# Sheet3.net
KiCad netlist of a schematic drawn in Altium Designer
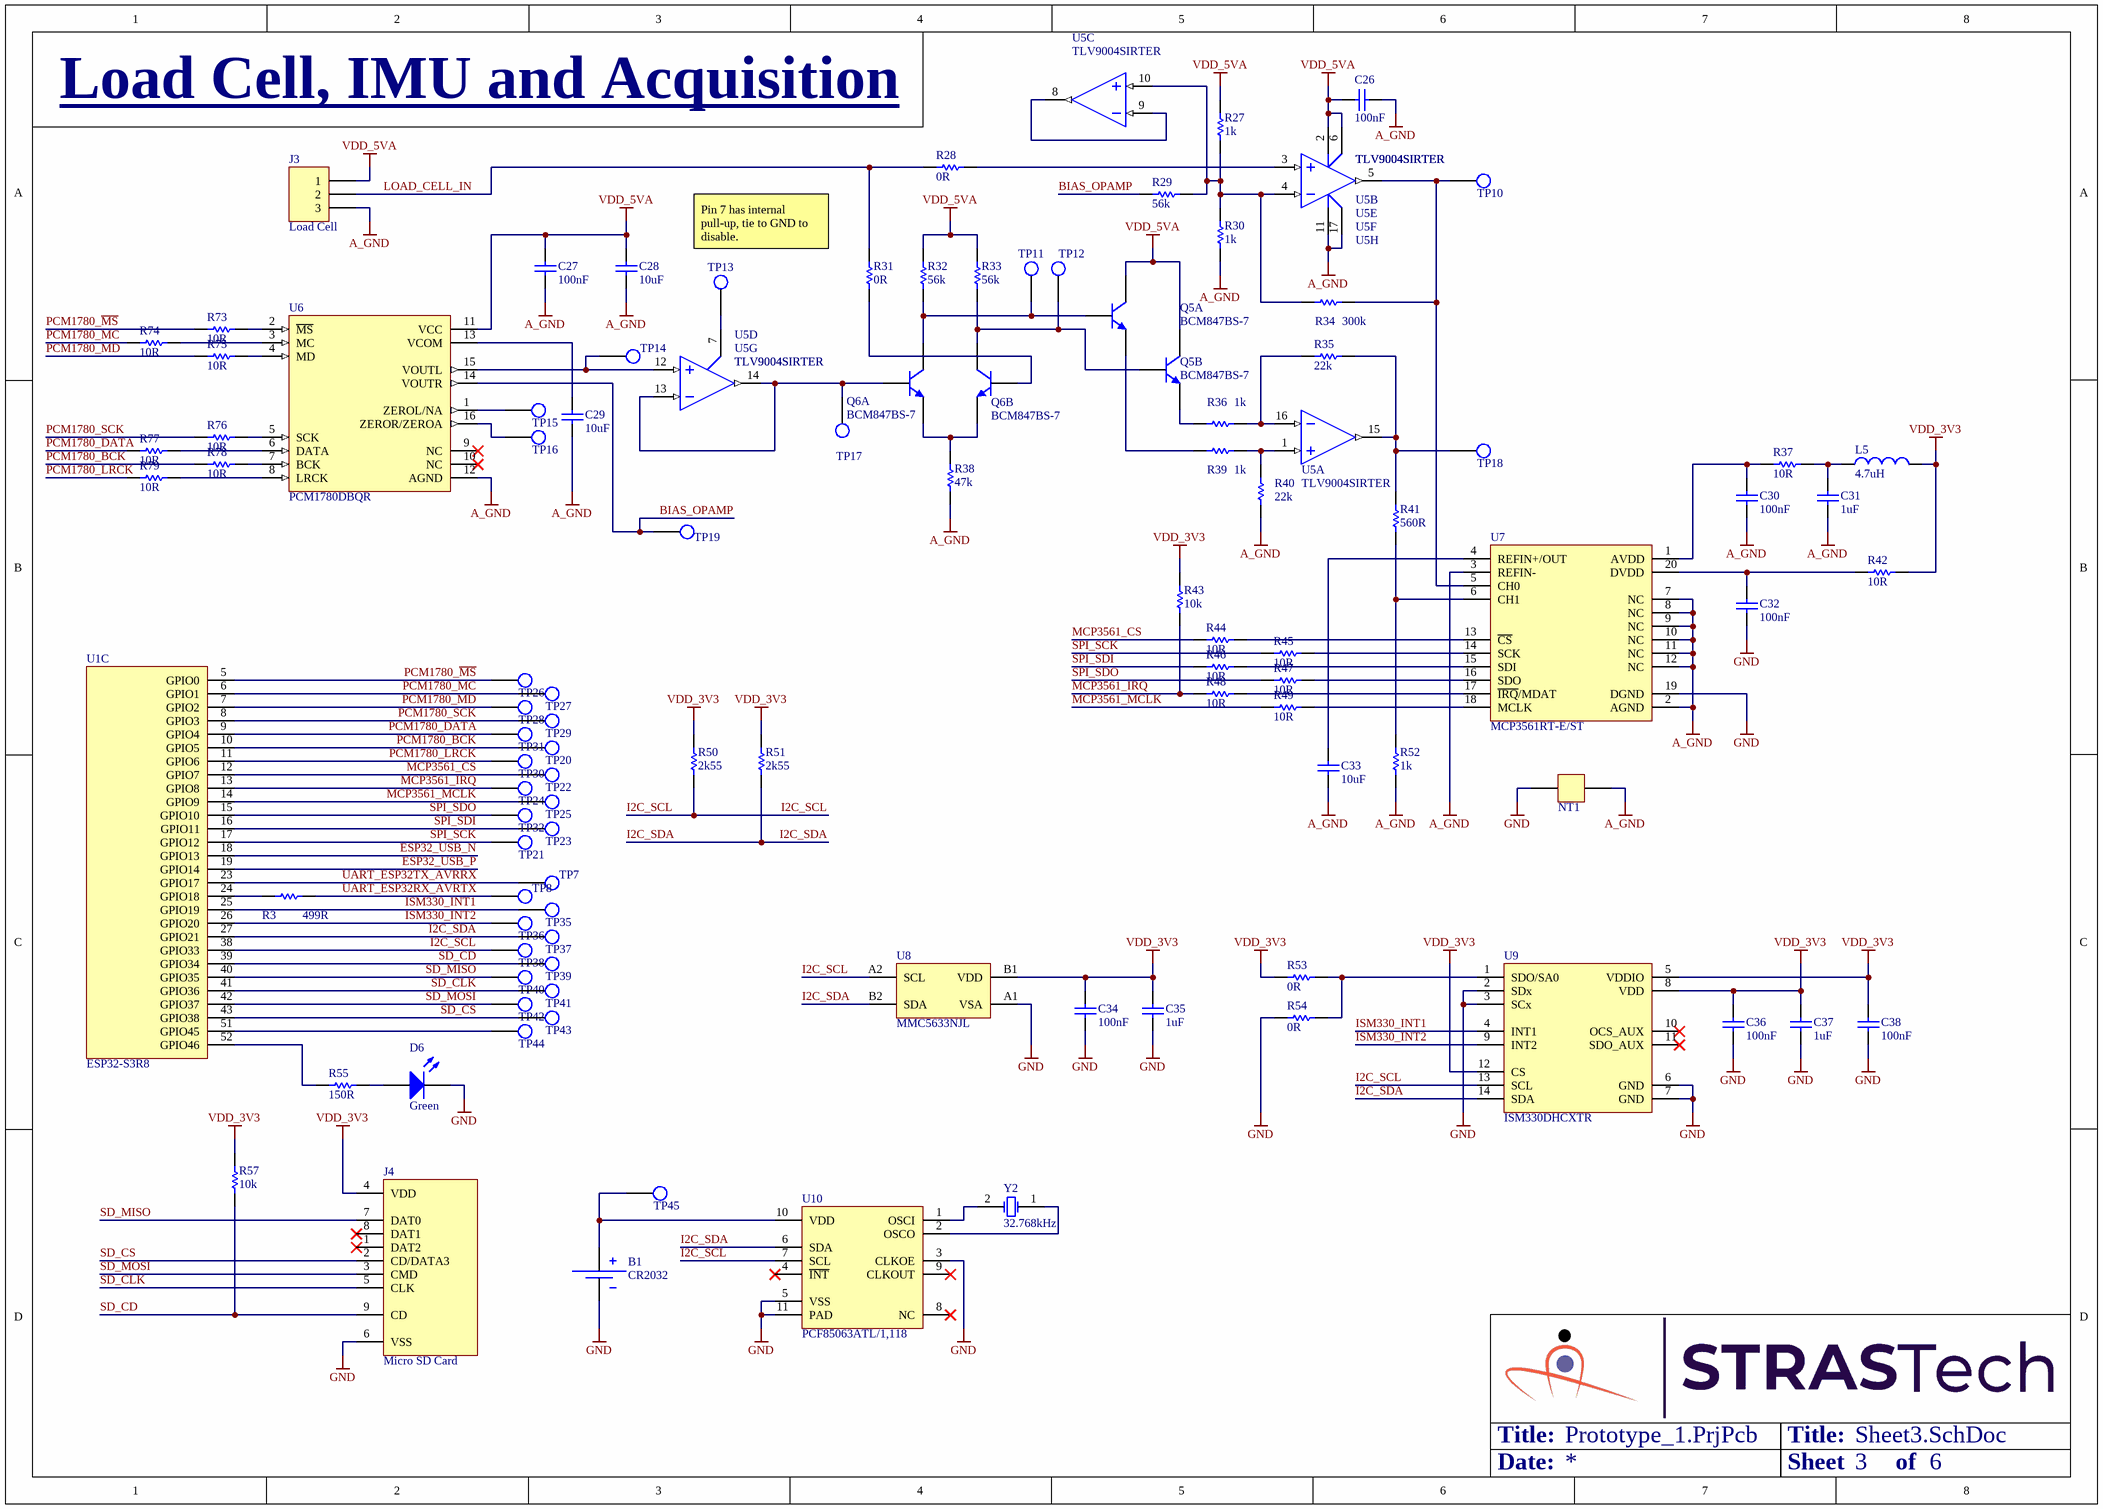
[diagram p0: Sheet3.SchDoc]

(export (version "E")
  (design (tool "Eeschema 10.0.6"))
  (components
    (comp (ref "B1")
      (value "CR2032")
      (footprint "Holder,Cell,CR2032,PCB,SMD")
      (description "Battery Retainer Coin, 20.0mm 1 Cell SMD (SMT) Tab")
      (fields
        (field (name "MANUFACTURER") "Keystone Electronics")
        (field (name "MANUFACTURER PART NUMBER") "3034")
        (field (name "CREATEDBY") "Judd Foster")
      )
      (libsource (lib "symbols") (part "Holder,Cell,CR2032,PCB,SMD"))
    )
    (comp (ref "C26")
      (value "100nF")
      (footprint "Cap,SMD,0402")
      (description "0.1µF ±10% 25V Ceramic Capacitor X7R 0402 (1005 Metric)")
      (fields
        (field (name "VENDOR PART NUMBER") "490-14603-1-ND")
        (field (name "MANUFACTURER") "Murata Electronics")
        (field (name "CREATEDBY") "Judd Foster")
      )
      (libsource (lib "symbols") (part "CAP,Cer,100nF,25VDC,X7R,0402"))
    )
    (comp (ref "C27")
      (value "100nF")
      (footprint "Cap,SMD,0402")
      (description "0.1µF ±10% 25V Ceramic Capacitor X7R 0402 (1005 Metric)")
      (fields
        (field (name "VENDOR PART NUMBER") "490-14603-1-ND")
        (field (name "MANUFACTURER") "Murata Electronics")
        (field (name "CREATEDBY") "Judd Foster")
      )
      (libsource (lib "symbols") (part "CAP,Cer,100nF,25VDC,X7R,0402"))
    )
    (comp (ref "C28")
      (value "10uF")
      (footprint "Cap,SMD,0402")
      (description "10 µF ±20% 10V Ceramic Capacitor X5R 0402 (1005 Metric)")
      (fields
        (field (name "VENDOR PART NUMBER") "1276-1450-1-ND")
        (field (name "MANUFACTURER") "Samsung Electro-Mechanics")
        (field (name "CREATEDBY") "Judd Foster")
      )
      (libsource (lib "symbols") (part "CAP,Cer,10uF,10VDC,X5R,0402"))
    )
    (comp (ref "C29")
      (value "10uF")
      (footprint "Cap,SMD,0402")
      (description "10 µF ±20% 10V Ceramic Capacitor X5R 0402 (1005 Metric)")
      (fields
        (field (name "VENDOR PART NUMBER") "1276-1450-1-ND")
        (field (name "MANUFACTURER") "Samsung Electro-Mechanics")
        (field (name "CREATEDBY") "Judd Foster")
      )
      (libsource (lib "symbols") (part "CAP,Cer,10uF,10VDC,X5R,0402"))
    )
    (comp (ref "C30")
      (value "100nF")
      (footprint "Cap,SMD,0402")
      (description "0.1µF ±10% 25V Ceramic Capacitor X7R 0402 (1005 Metric)")
      (fields
        (field (name "VENDOR PART NUMBER") "490-14603-1-ND")
        (field (name "MANUFACTURER") "Murata Electronics")
        (field (name "CREATEDBY") "Judd Foster")
      )
      (libsource (lib "symbols") (part "CAP,Cer,100nF,25VDC,X7R,0402"))
    )
    (comp (ref "C31")
      (value "1uF")
      (footprint "Cap,SMD,0402")
      (description "1 µF ±10% 35V Ceramic Capacitor X5R 0402 (1005 Metric)")
      (fields
        (field (name "VENDOR PART NUMBER") "445-9073-1-ND")
        (field (name "MANUFACTURER") "TDK Corporation")
        (field (name "CREATEDBY") "Judd Foster")
      )
      (libsource (lib "symbols") (part "CAP,Cer,1uF,35VDC,X5R,0402"))
    )
    (comp (ref "C32")
      (value "100nF")
      (footprint "Cap,SMD,0402")
      (description "0.1µF ±10% 25V Ceramic Capacitor X7R 0402 (1005 Metric)")
      (fields
        (field (name "VENDOR PART NUMBER") "490-14603-1-ND")
        (field (name "MANUFACTURER") "Murata Electronics")
        (field (name "CREATEDBY") "Judd Foster")
      )
      (libsource (lib "symbols") (part "CAP,Cer,100nF,25VDC,X7R,0402"))
    )
    (comp (ref "C33")
      (value "10uF")
      (footprint "Cap,SMD,0402")
      (description "10 µF ±20% 10V Ceramic Capacitor X5R 0402 (1005 Metric)")
      (fields
        (field (name "VENDOR PART NUMBER") "1276-1450-1-ND")
        (field (name "MANUFACTURER") "Samsung Electro-Mechanics")
        (field (name "CREATEDBY") "Judd Foster")
      )
      (libsource (lib "symbols") (part "CAP,Cer,10uF,10VDC,X5R,0402"))
    )
    (comp (ref "C34")
      (value "100nF")
      (footprint "Cap,SMD,0402")
      (description "0.1µF ±10% 25V Ceramic Capacitor X7R 0402 (1005 Metric)")
      (fields
        (field (name "VENDOR PART NUMBER") "490-14603-1-ND")
        (field (name "MANUFACTURER") "Murata Electronics")
        (field (name "CREATEDBY") "Judd Foster")
      )
      (libsource (lib "symbols") (part "CAP,Cer,100nF,25VDC,X7R,0402"))
    )
    (comp (ref "C35")
      (value "1uF")
      (footprint "Cap,SMD,0402")
      (description "1 µF ±10% 35V Ceramic Capacitor X5R 0402 (1005 Metric)")
      (fields
        (field (name "VENDOR PART NUMBER") "445-9073-1-ND")
        (field (name "MANUFACTURER") "TDK Corporation")
        (field (name "CREATEDBY") "Judd Foster")
      )
      (libsource (lib "symbols") (part "CAP,Cer,1uF,35VDC,X5R,0402"))
    )
    (comp (ref "C36")
      (value "100nF")
      (footprint "Cap,SMD,0402")
      (description "0.1µF ±10% 25V Ceramic Capacitor X7R 0402 (1005 Metric)")
      (fields
        (field (name "VENDOR PART NUMBER") "490-14603-1-ND")
        (field (name "MANUFACTURER") "Murata Electronics")
        (field (name "CREATEDBY") "Judd Foster")
      )
      (libsource (lib "symbols") (part "CAP,Cer,100nF,25VDC,X7R,0402"))
    )
    (comp (ref "C37")
      (value "1uF")
      (footprint "Cap,SMD,0402")
      (description "1 µF ±10% 35V Ceramic Capacitor X5R 0402 (1005 Metric)")
      (fields
        (field (name "VENDOR PART NUMBER") "445-9073-1-ND")
        (field (name "MANUFACTURER") "TDK Corporation")
        (field (name "CREATEDBY") "Judd Foster")
      )
      (libsource (lib "symbols") (part "CAP,Cer,1uF,35VDC,X5R,0402"))
    )
    (comp (ref "C38")
      (value "100nF")
      (footprint "Cap,SMD,0402")
      (description "0.1µF ±10% 25V Ceramic Capacitor X7R 0402 (1005 Metric)")
      (fields
        (field (name "VENDOR PART NUMBER") "490-14603-1-ND")
        (field (name "MANUFACTURER") "Murata Electronics")
        (field (name "CREATEDBY") "Judd Foster")
      )
      (libsource (lib "symbols") (part "CAP,Cer,100nF,25VDC,X7R,0402"))
    )
    (comp (ref "D6")
      (value "Green")
      (footprint "LED,0603")
      (description "Green 530nm LED Indication - Discrete 3V 0603 (1608 Metric)")
      (fields
        (field (name "MANUFACTURER") "Stanley Electric Co")
        (field (name "MANUFACTURER PART NUMBER") "THG1111C-0005-TR")
        (field (name "CREATEDBY") "Judd Foster")
      )
      (libsource (lib "symbols") (part "LED,Green,SMD,0603"))
    )
    (comp (ref "J3")
      (value "Term,Header,3 Pin,Top,2.54mm")
      (footprint "Term,Header,3Pin,2.54mm")
      (description "CONN HEADER VERT 3POS 2.54MM")
      (fields
        (field (name "VENDOR PART NUMBER") "732-5316-ND")
        (field (name "MANUFACTURER") "Würth Elektronik")
        (field (name "CREATED BY") "Judd Foster")
      )
      (libsource (lib "symbols") (part "Term,Header,3 Pin,Top,2.54mm"))
    )
    (comp (ref "J4")
      (value "Micro SD Card")
      (footprint "Conn,MicroSD,Push-Push,SMD")
      (description "9 (8 + 1) Position Card Connector Secure Digital - microSD™ Surface Mount, Right Angle Gold")
      (fields
        (field (name "MANUFACTURER") "GCT")
        (field (name "MANUFACTURER PART NUMBER") "MEM2075-00-140-01-A")
        (field (name "CREATEDBY") "Judd Foster")
      )
      (libsource (lib "symbols") (part "Conn,MicroSD,SMD,Push-Push"))
    )
    (comp (ref "L5")
      (value "4.7uH")
      (footprint "IND,0805")
      (description "4.7 µH Shielded Multilayer Inductor 80 mA 300mOhm 0805 (2012 Metric)")
      (fields
        (field (name "VENDOR PART NUMBER") "445-3169-1-ND")
        (field (name "MANUFACTURER") "TDK Corporation")
        (field (name "CREATEDBY") "Judd Foster")
      )
      (libsource (lib "symbols") (part "IND,4.7uH,80mA,Multilayer,0805"))
    )
    (comp (ref "NT1")
      (value "Net Tie")
      (footprint "Net Tie,20x60mil")
      (fields (field (name "CREATEDBY") "Makan Mousavi"))
      (libsource (lib "symbols") (part "Net Tie"))
    )
    (comp (ref "Q5")
      (value "BCM847BS-7")
      (footprint "SOT363")
      (fields
        (field (name "MANUFACTURER") "Diodes Incorporated")
        (field (name "VENDOR PART NUMBER") "31-BCM847BS-7CT-ND")
        (field (name "CREATEDBY") "Judd Foster")
      )
      (libsource (lib "symbols") (part "Trans,Array,NPN/NPN,Matched,45V,100mA,SOT-363"))
    )
    (comp (ref "Q6")
      (value "BCM847BS-7")
      (footprint "SOT363")
      (fields
        (field (name "MANUFACTURER") "Diodes Incorporated")
        (field (name "VENDOR PART NUMBER") "31-BCM847BS-7CT-ND")
        (field (name "CREATEDBY") "Judd Foster")
      )
      (libsource (lib "symbols") (part "Trans,Array,NPN/NPN,Matched,45V,100mA,SOT-363"))
    )
    (comp (ref "R3")
      (value "499R")
      (footprint "RES,0402")
      (description "499 Ohms ±1% 0.063W, 1/16W Chip Resistor 0402 (1005 Metric) Automotive AEC-Q200 Thick Film")
      (fields
        (field (name "MANUFACTURER") "Stackpole Electronics Inc")
        (field (name "MANUFACTURER PART NUMBER") "RMCF0402FT499R")
        (field (name "CREATEDBY") "Judd Foster")
      )
      (libsource (lib "symbols") (part "RES,499R,1%,0.063W,0402"))
    )
    (comp (ref "R27")
      (value "1k")
      (footprint "RES,0402")
      (description "1 kOhms ±5% 0.063W, 1/16W Chip Resistor 0402 (1005 Metric) Automotive AEC-Q200 Thick Film")
      (fields
        (field (name "VENDOR PART NUMBER") "RMCF0402JT1K00CT-ND")
        (field (name "MANUFACTURER") "Stackpole Electronics Inc")
        (field (name "CREATEDBY") "Judd Foster")
      )
      (libsource (lib "symbols") (part "RES,1k,5%,0.063W,0402"))
    )
    (comp (ref "R28")
      (value "0R")
      (footprint "RES,0402")
      (description "0 Ohms Jumper 0.1W, 1/10W Chip Resistor 0402 (1005 Metric) Automotive AEC-Q200 Thick Film")
      (fields
        (field (name "MANUFACTURER") "Panasonic Electronic Components")
        (field (name "MANUFACTURER PART NUMBER") "ERJ-2GE0R00X")
        (field (name "CREATEDBY") "Judd Foster")
      )
      (libsource (lib "symbols") (part "RES,0R0,0.1W,0402"))
    )
    (comp (ref "R29")
      (value "56k")
      (footprint "RES,0402")
      (description "56 kOhms ±1% 0.1W, 1/10W Chip Resistor 0402 (1005 Metric) Automotive AEC-Q200 Thick Film")
      (fields
        (field (name "MANUFACTURER") "Panasonic Electronic Components")
        (field (name "MANUFACTURER PART NUMBER") "ERJ-2RKF5602X")
        (field (name "CREATEDBY") "Judd Foster")
      )
      (libsource (lib "symbols") (part "RES,56k,1%,0.063W,0402"))
    )
    (comp (ref "R30")
      (value "1k")
      (footprint "RES,0402")
      (description "1 kOhms ±5% 0.063W, 1/16W Chip Resistor 0402 (1005 Metric) Automotive AEC-Q200 Thick Film")
      (fields
        (field (name "VENDOR PART NUMBER") "RMCF0402JT1K00CT-ND")
        (field (name "MANUFACTURER") "Stackpole Electronics Inc")
        (field (name "CREATEDBY") "Judd Foster")
      )
      (libsource (lib "symbols") (part "RES,1k,5%,0.063W,0402"))
    )
    (comp (ref "R31")
      (value "0R")
      (footprint "RES,0402")
      (description "0 Ohms Jumper 0.1W, 1/10W Chip Resistor 0402 (1005 Metric) Automotive AEC-Q200 Thick Film")
      (fields
        (field (name "MANUFACTURER") "Panasonic Electronic Components")
        (field (name "MANUFACTURER PART NUMBER") "ERJ-2GE0R00X")
        (field (name "CREATEDBY") "Judd Foster")
      )
      (libsource (lib "symbols") (part "RES,0R0,0.1W,0402"))
    )
    (comp (ref "R32")
      (value "56k")
      (footprint "RES,0402")
      (description "56 kOhms ±1% 0.1W, 1/10W Chip Resistor 0402 (1005 Metric) Automotive AEC-Q200 Thick Film")
      (fields
        (field (name "MANUFACTURER") "Panasonic Electronic Components")
        (field (name "MANUFACTURER PART NUMBER") "ERJ-2RKF5602X")
        (field (name "CREATEDBY") "Judd Foster")
      )
      (libsource (lib "symbols") (part "RES,56k,1%,0.063W,0402"))
    )
    (comp (ref "R33")
      (value "56k")
      (footprint "RES,0402")
      (description "56 kOhms ±1% 0.1W, 1/10W Chip Resistor 0402 (1005 Metric) Automotive AEC-Q200 Thick Film")
      (fields
        (field (name "MANUFACTURER") "Panasonic Electronic Components")
        (field (name "MANUFACTURER PART NUMBER") "ERJ-2RKF5602X")
        (field (name "CREATEDBY") "Judd Foster")
      )
      (libsource (lib "symbols") (part "RES,56k,1%,0.063W,0402"))
    )
    (comp (ref "R34")
      (value "300k")
      (footprint "RES,0402")
      (description "300 kOhms ±1% 0.063W, 1/16W Chip Resistor 0402 (1005 Metric) Automotive AEC-Q200 Thick Film")
      (fields
        (field (name "MANUFACTURER") "Stackpole Electronics Inc")
        (field (name "MANUFACTURER PART NUMBER") "RMCF0402FT300K")
        (field (name "CREATEDBY") "Judd Foster")
      )
      (libsource (lib "symbols") (part "RES,300k,1%,0.063W,0402"))
    )
    (comp (ref "R35")
      (value "22k")
      (footprint "RES,0402")
      (description "22 kOhms ±1% 0.063W, 1/16W Chip Resistor 0402 (1005 Metric) Automotive AEC-Q200 Thick Film")
      (fields
        (field (name "VENDOR PART NUMBER") "RMCF0402FT22K0CT-ND")
        (field (name "MANUFACTURER") "Stackpole Electronics Inc")
        (field (name "CREATEDBY") "Judd Foster")
      )
      (libsource (lib "symbols") (part "RES,22k,1%,0.063W,0402"))
    )
    (comp (ref "R36")
      (value "1k")
      (footprint "RES,0402")
      (description "1 kOhms ±5% 0.063W, 1/16W Chip Resistor 0402 (1005 Metric) Automotive AEC-Q200 Thick Film")
      (fields
        (field (name "VENDOR PART NUMBER") "RMCF0402JT1K00CT-ND")
        (field (name "MANUFACTURER") "Stackpole Electronics Inc")
        (field (name "CREATEDBY") "Judd Foster")
      )
      (libsource (lib "symbols") (part "RES,1k,5%,0.063W,0402"))
    )
    (comp (ref "R37")
      (value "10R")
      (footprint "RES,0402")
      (description "10 Ohms ±1% 0.063W, 1/16W Chip Resistor 0402 (1005 Metric) Automotive AEC-Q200 Thick Film")
      (fields
        (field (name "MANUFACTURER") "Panasonic Electronic Components")
        (field (name "MANUFACTURER PART NUMBER") "ERJ-2RKF10R0X")
        (field (name "CREATEDBY") "Judd Foster")
      )
      (libsource (lib "symbols") (part "RES,10R,1%,0.063W,0402"))
    )
    (comp (ref "R38")
      (value "47k")
      (footprint "RES,0402")
      (description "47 kOhms ±1% 0.1W, 1/10W Chip Resistor 0402 (1005 Metric) Automotive AEC-Q200 Thick Film")
      (fields
        (field (name "MANUFACTURER") "Panasonic Electronic Components")
        (field (name "MANUFACTURER PART NUMBER") "ERJ-2RKF4702X")
        (field (name "CREATEDBY") "Judd Foster")
      )
      (libsource (lib "symbols") (part "RES,47k,1%,0.1W,0402"))
    )
    (comp (ref "R39")
      (value "1k")
      (footprint "RES,0402")
      (description "1 kOhms ±5% 0.063W, 1/16W Chip Resistor 0402 (1005 Metric) Automotive AEC-Q200 Thick Film")
      (fields
        (field (name "VENDOR PART NUMBER") "RMCF0402JT1K00CT-ND")
        (field (name "MANUFACTURER") "Stackpole Electronics Inc")
        (field (name "CREATEDBY") "Judd Foster")
      )
      (libsource (lib "symbols") (part "RES,1k,5%,0.063W,0402"))
    )
    (comp (ref "R40")
      (value "22k")
      (footprint "RES,0402")
      (description "22 kOhms ±1% 0.063W, 1/16W Chip Resistor 0402 (1005 Metric) Automotive AEC-Q200 Thick Film")
      (fields
        (field (name "VENDOR PART NUMBER") "RMCF0402FT22K0CT-ND")
        (field (name "MANUFACTURER") "Stackpole Electronics Inc")
        (field (name "CREATEDBY") "Judd Foster")
      )
      (libsource (lib "symbols") (part "RES,22k,1%,0.063W,0402"))
    )
    (comp (ref "R41")
      (value "560R")
      (footprint "RES,0402")
      (fields
        (field (name "MANUFACTURER") "TE Connectivity Passive Product")
        (field (name "MANUFACTURER PART NUMBER") "CRGCQ0402F560R")
        (field (name "VENDOR PART NUMBER") "A129624CT-ND")
        (field (name "CREATEDBY") "Judd Foster")
      )
      (libsource (lib "symbols") (part "RES,560R,1%,0.063W,0402"))
    )
    (comp (ref "R42")
      (value "10R")
      (footprint "RES,0402")
      (description "10 Ohms ±1% 0.063W, 1/16W Chip Resistor 0402 (1005 Metric) Automotive AEC-Q200 Thick Film")
      (fields
        (field (name "MANUFACTURER") "Panasonic Electronic Components")
        (field (name "MANUFACTURER PART NUMBER") "ERJ-2RKF10R0X")
        (field (name "CREATEDBY") "Judd Foster")
      )
      (libsource (lib "symbols") (part "RES,10R,1%,0.063W,0402"))
    )
    (comp (ref "R43")
      (value "10k")
      (footprint "RES,0402")
      (description "10 kOhms ±5% 0.063W, 1/16W Chip Resistor 0402 (1005 Metric) Automotive AEC-Q200 Thick Film")
      (fields
        (field (name "VENDOR PART NUMBER") "RMCF0402JT10K0CT-ND")
        (field (name "MANUFACTURER") "Stackpole Electronics Inc")
        (field (name "CREATEDBY") "Judd Foster")
      )
      (libsource (lib "symbols") (part "RES,10k,5%,0.063W,0402"))
    )
    (comp (ref "R44")
      (value "10R")
      (footprint "RES,0402")
      (description "10 Ohms ±1% 0.063W, 1/16W Chip Resistor 0402 (1005 Metric) Automotive AEC-Q200 Thick Film")
      (fields
        (field (name "MANUFACTURER") "Panasonic Electronic Components")
        (field (name "MANUFACTURER PART NUMBER") "ERJ-2RKF10R0X")
        (field (name "CREATEDBY") "Judd Foster")
      )
      (libsource (lib "symbols") (part "RES,10R,1%,0.063W,0402"))
    )
    (comp (ref "R45")
      (value "10R")
      (footprint "RES,0402")
      (description "10 Ohms ±1% 0.063W, 1/16W Chip Resistor 0402 (1005 Metric) Automotive AEC-Q200 Thick Film")
      (fields
        (field (name "MANUFACTURER") "Panasonic Electronic Components")
        (field (name "MANUFACTURER PART NUMBER") "ERJ-2RKF10R0X")
        (field (name "CREATEDBY") "Judd Foster")
      )
      (libsource (lib "symbols") (part "RES,10R,1%,0.063W,0402"))
    )
    (comp (ref "R46")
      (value "10R")
      (footprint "RES,0402")
      (description "10 Ohms ±1% 0.063W, 1/16W Chip Resistor 0402 (1005 Metric) Automotive AEC-Q200 Thick Film")
      (fields
        (field (name "MANUFACTURER") "Panasonic Electronic Components")
        (field (name "MANUFACTURER PART NUMBER") "ERJ-2RKF10R0X")
        (field (name "CREATEDBY") "Judd Foster")
      )
      (libsource (lib "symbols") (part "RES,10R,1%,0.063W,0402"))
    )
    (comp (ref "R47")
      (value "10R")
      (footprint "RES,0402")
      (description "10 Ohms ±1% 0.063W, 1/16W Chip Resistor 0402 (1005 Metric) Automotive AEC-Q200 Thick Film")
      (fields
        (field (name "MANUFACTURER") "Panasonic Electronic Components")
        (field (name "MANUFACTURER PART NUMBER") "ERJ-2RKF10R0X")
        (field (name "CREATEDBY") "Judd Foster")
      )
      (libsource (lib "symbols") (part "RES,10R,1%,0.063W,0402"))
    )
    (comp (ref "R48")
      (value "10R")
      (footprint "RES,0402")
      (description "10 Ohms ±1% 0.063W, 1/16W Chip Resistor 0402 (1005 Metric) Automotive AEC-Q200 Thick Film")
      (fields
        (field (name "MANUFACTURER") "Panasonic Electronic Components")
        (field (name "MANUFACTURER PART NUMBER") "ERJ-2RKF10R0X")
        (field (name "CREATEDBY") "Judd Foster")
      )
      (libsource (lib "symbols") (part "RES,10R,1%,0.063W,0402"))
    )
    (comp (ref "R49")
      (value "10R")
      (footprint "RES,0402")
      (description "10 Ohms ±1% 0.063W, 1/16W Chip Resistor 0402 (1005 Metric) Automotive AEC-Q200 Thick Film")
      (fields
        (field (name "MANUFACTURER") "Panasonic Electronic Components")
        (field (name "MANUFACTURER PART NUMBER") "ERJ-2RKF10R0X")
        (field (name "CREATEDBY") "Judd Foster")
      )
      (libsource (lib "symbols") (part "RES,10R,1%,0.063W,0402"))
    )
    (comp (ref "R50")
      (value "2k55")
      (footprint "RES,0402")
      (description "2.55 kOhms ±1% 0.063W, 1/16W Chip Resistor 0402 (1005 Metric) Automotive AEC-Q200 Thick Film")
      (fields
        (field (name "MANUFACTURER") "Stackpole Electronics Inc")
        (field (name "MANUFACTURER PART NUMBER") "RMCF0402FT2K55")
        (field (name "CREATEDBY") "Judd Foster")
      )
      (libsource (lib "symbols") (part "RES,2k55,1%,0.063W,0402"))
    )
    (comp (ref "R51")
      (value "2k55")
      (footprint "RES,0402")
      (description "2.55 kOhms ±1% 0.063W, 1/16W Chip Resistor 0402 (1005 Metric) Automotive AEC-Q200 Thick Film")
      (fields
        (field (name "MANUFACTURER") "Stackpole Electronics Inc")
        (field (name "MANUFACTURER PART NUMBER") "RMCF0402FT2K55")
        (field (name "CREATEDBY") "Judd Foster")
      )
      (libsource (lib "symbols") (part "RES,2k55,1%,0.063W,0402"))
    )
    (comp (ref "R52")
      (value "1k")
      (footprint "RES,0402")
      (description "1 kOhms ±5% 0.063W, 1/16W Chip Resistor 0402 (1005 Metric) Automotive AEC-Q200 Thick Film")
      (fields
        (field (name "VENDOR PART NUMBER") "RMCF0402JT1K00CT-ND")
        (field (name "MANUFACTURER") "Stackpole Electronics Inc")
        (field (name "CREATEDBY") "Judd Foster")
      )
      (libsource (lib "symbols") (part "RES,1k,5%,0.063W,0402"))
    )
    (comp (ref "R53")
      (value "0R")
      (footprint "RES,0402")
      (description "0 Ohms Jumper 0.1W, 1/10W Chip Resistor 0402 (1005 Metric) Automotive AEC-Q200 Thick Film")
      (fields
        (field (name "MANUFACTURER") "Panasonic Electronic Components")
        (field (name "MANUFACTURER PART NUMBER") "ERJ-2GE0R00X")
        (field (name "CREATEDBY") "Judd Foster")
      )
      (libsource (lib "symbols") (part "RES,0R0,0.1W,0402"))
    )
    (comp (ref "R54")
      (value "0R")
      (footprint "RES,0402")
      (description "0 Ohms Jumper 0.1W, 1/10W Chip Resistor 0402 (1005 Metric) Automotive AEC-Q200 Thick Film")
      (fields
        (field (name "MANUFACTURER") "Panasonic Electronic Components")
        (field (name "MANUFACTURER PART NUMBER") "ERJ-2GE0R00X")
        (field (name "CREATEDBY") "Judd Foster")
      )
      (libsource (lib "symbols") (part "RES,0R0,0.1W,0402"))
    )
    (comp (ref "R55")
      (value "150R")
      (footprint "RES,0402")
      (fields
        (field (name "MANUFACTURER") "TE Connectivity Passive Product")
        (field (name "MANUFACTURER PART NUMBER") "CRGCQ0402F150R")
        (field (name "VENDOR PART NUMBER") "A129617CT-ND")
        (field (name "CREATEDBY") "Judd Foster")
      )
      (libsource (lib "symbols") (part "RES,150R,1%,0.1W,0402"))
    )
    (comp (ref "R57")
      (value "10k")
      (footprint "RES,0402")
      (description "10 kOhms ±5% 0.063W, 1/16W Chip Resistor 0402 (1005 Metric) Automotive AEC-Q200 Thick Film")
      (fields
        (field (name "VENDOR PART NUMBER") "RMCF0402JT10K0CT-ND")
        (field (name "MANUFACTURER") "Stackpole Electronics Inc")
        (field (name "CREATEDBY") "Judd Foster")
      )
      (libsource (lib "symbols") (part "RES,10k,5%,0.063W,0402"))
    )
    (comp (ref "R73")
      (value "10R")
      (footprint "RES,0402")
      (description "10 Ohms ±1% 0.063W, 1/16W Chip Resistor 0402 (1005 Metric) Automotive AEC-Q200 Thick Film")
      (fields
        (field (name "MANUFACTURER") "Panasonic Electronic Components")
        (field (name "MANUFACTURER PART NUMBER") "ERJ-2RKF10R0X")
        (field (name "CREATEDBY") "Judd Foster")
      )
      (libsource (lib "symbols") (part "RES,10R,1%,0.063W,0402"))
    )
    (comp (ref "R74")
      (value "10R")
      (footprint "RES,0402")
      (description "10 Ohms ±1% 0.063W, 1/16W Chip Resistor 0402 (1005 Metric) Automotive AEC-Q200 Thick Film")
      (fields
        (field (name "MANUFACTURER") "Panasonic Electronic Components")
        (field (name "MANUFACTURER PART NUMBER") "ERJ-2RKF10R0X")
        (field (name "CREATEDBY") "Judd Foster")
      )
      (libsource (lib "symbols") (part "RES,10R,1%,0.063W,0402"))
    )
    (comp (ref "R75")
      (value "10R")
      (footprint "RES,0402")
      (description "10 Ohms ±1% 0.063W, 1/16W Chip Resistor 0402 (1005 Metric) Automotive AEC-Q200 Thick Film")
      (fields
        (field (name "MANUFACTURER") "Panasonic Electronic Components")
        (field (name "MANUFACTURER PART NUMBER") "ERJ-2RKF10R0X")
        (field (name "CREATEDBY") "Judd Foster")
      )
      (libsource (lib "symbols") (part "RES,10R,1%,0.063W,0402"))
    )
    (comp (ref "R76")
      (value "10R")
      (footprint "RES,0402")
      (description "10 Ohms ±1% 0.063W, 1/16W Chip Resistor 0402 (1005 Metric) Automotive AEC-Q200 Thick Film")
      (fields
        (field (name "MANUFACTURER") "Panasonic Electronic Components")
        (field (name "MANUFACTURER PART NUMBER") "ERJ-2RKF10R0X")
        (field (name "CREATEDBY") "Judd Foster")
      )
      (libsource (lib "symbols") (part "RES,10R,1%,0.063W,0402"))
    )
    (comp (ref "R77")
      (value "10R")
      (footprint "RES,0402")
      (description "10 Ohms ±1% 0.063W, 1/16W Chip Resistor 0402 (1005 Metric) Automotive AEC-Q200 Thick Film")
      (fields
        (field (name "MANUFACTURER") "Panasonic Electronic Components")
        (field (name "MANUFACTURER PART NUMBER") "ERJ-2RKF10R0X")
        (field (name "CREATEDBY") "Judd Foster")
      )
      (libsource (lib "symbols") (part "RES,10R,1%,0.063W,0402"))
    )
    (comp (ref "R78")
      (value "10R")
      (footprint "RES,0402")
      (description "10 Ohms ±1% 0.063W, 1/16W Chip Resistor 0402 (1005 Metric) Automotive AEC-Q200 Thick Film")
      (fields
        (field (name "MANUFACTURER") "Panasonic Electronic Components")
        (field (name "MANUFACTURER PART NUMBER") "ERJ-2RKF10R0X")
        (field (name "CREATEDBY") "Judd Foster")
      )
      (libsource (lib "symbols") (part "RES,10R,1%,0.063W,0402"))
    )
    (comp (ref "R79")
      (value "10R")
      (footprint "RES,0402")
      (description "10 Ohms ±1% 0.063W, 1/16W Chip Resistor 0402 (1005 Metric) Automotive AEC-Q200 Thick Film")
      (fields
        (field (name "MANUFACTURER") "Panasonic Electronic Components")
        (field (name "MANUFACTURER PART NUMBER") "ERJ-2RKF10R0X")
        (field (name "CREATEDBY") "Judd Foster")
      )
      (libsource (lib "symbols") (part "RES,10R,1%,0.063W,0402"))
    )
    (comp (ref "TP7")
      (value "TESTPOINT")
      (footprint "testpoint,smd,round,1mm")
      (description "PCB Testpoint")
      (fields (field (name "CREATEDBY") "Judd Foster"))
      (libsource (lib "symbols") (part "TESTPOINT"))
    )
    (comp (ref "TP8")
      (value "TESTPOINT")
      (footprint "testpoint,smd,round,1mm")
      (description "PCB Testpoint")
      (fields (field (name "CREATEDBY") "Judd Foster"))
      (libsource (lib "symbols") (part "TESTPOINT"))
    )
    (comp (ref "TP10")
      (value "TESTPOINT")
      (footprint "testpoint,smd,round,1mm")
      (description "PCB Testpoint")
      (fields (field (name "CREATEDBY") "Judd Foster"))
      (libsource (lib "symbols") (part "TESTPOINT"))
    )
    (comp (ref "TP11")
      (value "TESTPOINT")
      (footprint "testpoint,smd,round,1mm")
      (description "PCB Testpoint")
      (fields (field (name "CREATEDBY") "Judd Foster"))
      (libsource (lib "symbols") (part "TESTPOINT"))
    )
    (comp (ref "TP12")
      (value "TESTPOINT")
      (footprint "testpoint,smd,round,1mm")
      (description "PCB Testpoint")
      (fields (field (name "CREATEDBY") "Judd Foster"))
      (libsource (lib "symbols") (part "TESTPOINT"))
    )
    (comp (ref "TP13")
      (value "TESTPOINT")
      (footprint "testpoint,smd,round,1mm")
      (description "PCB Testpoint")
      (fields (field (name "CREATEDBY") "Judd Foster"))
      (libsource (lib "symbols") (part "TESTPOINT"))
    )
    (comp (ref "TP14")
      (value "TESTPOINT")
      (footprint "testpoint,smd,round,1mm")
      (description "PCB Testpoint")
      (fields (field (name "CREATEDBY") "Judd Foster"))
      (libsource (lib "symbols") (part "TESTPOINT"))
    )
    (comp (ref "TP15")
      (value "TESTPOINT")
      (footprint "testpoint,smd,round,1mm")
      (description "PCB Testpoint")
      (fields (field (name "CREATEDBY") "Judd Foster"))
      (libsource (lib "symbols") (part "TESTPOINT"))
    )
    (comp (ref "TP16")
      (value "TESTPOINT")
      (footprint "testpoint,smd,round,1mm")
      (description "PCB Testpoint")
      (fields (field (name "CREATEDBY") "Judd Foster"))
      (libsource (lib "symbols") (part "TESTPOINT"))
    )
    (comp (ref "TP17")
      (value "TESTPOINT")
      (footprint "testpoint,smd,round,1mm")
      (description "PCB Testpoint")
      (fields (field (name "CREATEDBY") "Judd Foster"))
      (libsource (lib "symbols") (part "TESTPOINT"))
    )
    (comp (ref "TP18")
      (value "TESTPOINT")
      (footprint "testpoint,smd,round,1mm")
      (description "PCB Testpoint")
      (fields (field (name "CREATEDBY") "Judd Foster"))
      (libsource (lib "symbols") (part "TESTPOINT"))
    )
    (comp (ref "TP19")
      (value "TESTPOINT")
      (footprint "testpoint,smd,round,1mm")
      (description "PCB Testpoint")
      (fields (field (name "CREATEDBY") "Judd Foster"))
      (libsource (lib "symbols") (part "TESTPOINT"))
    )
    (comp (ref "TP20")
      (value "TESTPOINT")
      (footprint "testpoint,smd,round,1mm")
      (description "PCB Testpoint")
      (fields (field (name "CREATEDBY") "Judd Foster"))
      (libsource (lib "symbols") (part "TESTPOINT"))
    )
    (comp (ref "TP21")
      (value "TESTPOINT")
      (footprint "testpoint,smd,round,1mm")
      (description "PCB Testpoint")
      (fields (field (name "CREATEDBY") "Judd Foster"))
      (libsource (lib "symbols") (part "TESTPOINT"))
    )
    (comp (ref "TP22")
      (value "TESTPOINT")
      (footprint "testpoint,smd,round,1mm")
      (description "PCB Testpoint")
      (fields (field (name "CREATEDBY") "Judd Foster"))
      (libsource (lib "symbols") (part "TESTPOINT"))
    )
    (comp (ref "TP23")
      (value "TESTPOINT")
      (footprint "testpoint,smd,round,1mm")
      (description "PCB Testpoint")
      (fields (field (name "CREATEDBY") "Judd Foster"))
      (libsource (lib "symbols") (part "TESTPOINT"))
    )
    (comp (ref "TP24")
      (value "TESTPOINT")
      (footprint "testpoint,smd,round,1mm")
      (description "PCB Testpoint")
      (fields (field (name "CREATEDBY") "Judd Foster"))
      (libsource (lib "symbols") (part "TESTPOINT"))
    )
    (comp (ref "TP25")
      (value "TESTPOINT")
      (footprint "testpoint,smd,round,1mm")
      (description "PCB Testpoint")
      (fields (field (name "CREATEDBY") "Judd Foster"))
      (libsource (lib "symbols") (part "TESTPOINT"))
    )
    (comp (ref "TP26")
      (value "TESTPOINT")
      (footprint "testpoint,smd,round,1mm")
      (description "PCB Testpoint")
      (fields (field (name "CREATEDBY") "Judd Foster"))
      (libsource (lib "symbols") (part "TESTPOINT"))
    )
    (comp (ref "TP27")
      (value "TESTPOINT")
      (footprint "testpoint,smd,round,1mm")
      (description "PCB Testpoint")
      (fields (field (name "CREATEDBY") "Judd Foster"))
      (libsource (lib "symbols") (part "TESTPOINT"))
    )
    (comp (ref "TP28")
      (value "TESTPOINT")
      (footprint "testpoint,smd,round,1mm")
      (description "PCB Testpoint")
      (fields (field (name "CREATEDBY") "Judd Foster"))
      (libsource (lib "symbols") (part "TESTPOINT"))
    )
    (comp (ref "TP29")
      (value "TESTPOINT")
      (footprint "testpoint,smd,round,1mm")
      (description "PCB Testpoint")
      (fields (field (name "CREATEDBY") "Judd Foster"))
      (libsource (lib "symbols") (part "TESTPOINT"))
    )
    (comp (ref "TP30")
      (value "TESTPOINT")
      (footprint "testpoint,smd,round,1mm")
      (description "PCB Testpoint")
      (fields (field (name "CREATEDBY") "Judd Foster"))
      (libsource (lib "symbols") (part "TESTPOINT"))
    )
    (comp (ref "TP31")
      (value "TESTPOINT")
      (footprint "testpoint,smd,round,1mm")
      (description "PCB Testpoint")
      (fields (field (name "CREATEDBY") "Judd Foster"))
      (libsource (lib "symbols") (part "TESTPOINT"))
    )
    (comp (ref "TP32")
      (value "TESTPOINT")
      (footprint "testpoint,smd,round,1mm")
      (description "PCB Testpoint")
      (fields (field (name "CREATEDBY") "Judd Foster"))
      (libsource (lib "symbols") (part "TESTPOINT"))
    )
    (comp (ref "TP35")
      (value "TESTPOINT")
      (footprint "testpoint,smd,round,1mm")
      (description "PCB Testpoint")
      (fields (field (name "CREATEDBY") "Judd Foster"))
      (libsource (lib "symbols") (part "TESTPOINT"))
    )
    (comp (ref "TP36")
      (value "TESTPOINT")
      (footprint "testpoint,smd,round,1mm")
      (description "PCB Testpoint")
      (fields (field (name "CREATEDBY") "Judd Foster"))
      (libsource (lib "symbols") (part "TESTPOINT"))
    )
    (comp (ref "TP37")
      (value "TESTPOINT")
      (footprint "testpoint,smd,round,1mm")
      (description "PCB Testpoint")
      (fields (field (name "CREATEDBY") "Judd Foster"))
      (libsource (lib "symbols") (part "TESTPOINT"))
    )
    (comp (ref "TP38")
      (value "TESTPOINT")
      (footprint "testpoint,smd,round,1mm")
      (description "PCB Testpoint")
      (fields (field (name "CREATEDBY") "Judd Foster"))
      (libsource (lib "symbols") (part "TESTPOINT"))
    )
    (comp (ref "TP39")
      (value "TESTPOINT")
      (footprint "testpoint,smd,round,1mm")
      (description "PCB Testpoint")
      (fields (field (name "CREATEDBY") "Judd Foster"))
      (libsource (lib "symbols") (part "TESTPOINT"))
    )
    (comp (ref "TP40")
      (value "TESTPOINT")
      (footprint "testpoint,smd,round,1mm")
      (description "PCB Testpoint")
      (fields (field (name "CREATEDBY") "Judd Foster"))
      (libsource (lib "symbols") (part "TESTPOINT"))
    )
    (comp (ref "TP41")
      (value "TESTPOINT")
      (footprint "testpoint,smd,round,1mm")
      (description "PCB Testpoint")
      (fields (field (name "CREATEDBY") "Judd Foster"))
      (libsource (lib "symbols") (part "TESTPOINT"))
    )
    (comp (ref "TP42")
      (value "TESTPOINT")
      (footprint "testpoint,smd,round,1mm")
      (description "PCB Testpoint")
      (fields (field (name "CREATEDBY") "Judd Foster"))
      (libsource (lib "symbols") (part "TESTPOINT"))
    )
    (comp (ref "TP43")
      (value "TESTPOINT")
      (footprint "testpoint,smd,round,1mm")
      (description "PCB Testpoint")
      (fields (field (name "CREATEDBY") "Judd Foster"))
      (libsource (lib "symbols") (part "TESTPOINT"))
    )
    (comp (ref "TP44")
      (value "TESTPOINT")
      (footprint "testpoint,smd,round,1mm")
      (description "PCB Testpoint")
      (fields (field (name "CREATEDBY") "Judd Foster"))
      (libsource (lib "symbols") (part "TESTPOINT"))
    )
    (comp (ref "TP45")
      (value "TESTPOINT")
      (footprint "testpoint,smd,round,1mm")
      (description "PCB Testpoint")
      (fields (field (name "CREATEDBY") "Judd Foster"))
      (libsource (lib "symbols") (part "TESTPOINT"))
    )
    (comp (ref "U1")
      (value "ESP32-S3R8")
      (footprint "IC,QFN-56,7X7,P0.4MM")
      (fields
        (field (name "MANUFACTURER") "Espressif Systems")
        (field (name "VENDOR PART NUMBER") "1904-ESP32-S3R8-ND")
        (field (name "CREATEDBY") "Judd Foster")
      )
      (libsource (lib "symbols") (part "ESP32-S3R8"))
    )
    (comp (ref "U5")
      (value "TLV9004SIRTER")
      (footprint "IC,QFN-16,3x3")
      (description "General Purpose Amplifier 4 Circuit Rail-to-Rail 16-WQFN (3x3)")
      (fields
        (field (name "MANUFACTURER") "Texas Instruments")
        (field (name "VENDOR PART NUMBER") "296-51829-1-ND")
        (field (name "CREATEDBY") "Judd Foster")
      )
      (libsource (lib "symbols") (part "TLV9004SIRTER"))
    )
    (comp (ref "U6")
      (value "PCM1780DBQR")
      (footprint "IC,TSSOP-16,W3.9,P0.635MM")
      (description "DAC, Audio 24 b 200k I²S 16-SSOP")
      (fields
        (field (name "MANUFACTURER") "Texas Instruments")
        (field (name "VENDOR PART NUMBER") "296-41373-1-ND")
        (field (name "CREATEDBY") "Judd Foster")
      )
      (libsource (lib "symbols") (part "PCM1780DBQR"))
    )
    (comp (ref "U7")
      (value "MCP3561RT-E/ST")
      (footprint "IC,TSSOP-20,W4.4")
      (description "24 Bit Analog to Digital Converter 1 Input 1 Sigma-Delta 20-TSSOP")
      (fields
        (field (name "VENDOR PART NUMBER") "150-MCP3561RT-E/STCT-ND")
        (field (name "MANUFACTURER") "Microchip Technology")
        (field (name "CREATEDBY") "Judd Foster")
      )
      (libsource (lib "symbols") (part "MCP3561RT-E/ST"))
    )
    (comp (ref "U8")
      (value "MMC5633NJL")
      (footprint "IC,WLP,2x2,P0.4mm")
      (description "Magnetoresistive Sensor X, Y, Z Axis 4-WLP (0.85x0.85)")
      (fields
        (field (name "MANUFACTURER") "Memsic Inc.")
        (field (name "VENDOR PART NUMBER") "1267-MMC5633NJLCT-ND")
        (field (name "CREATEDBY") "Judd Foster")
      )
      (libsource (lib "symbols") (part "MMC5633NJL"))
    )
    (comp (ref "U9")
      (value "ISM330DHCXTR")
      (footprint "IC,LGA-14L,2.5x3mm")
      (description "Accelerometer, Gyroscope, Temperature, 6 Axis Sensor I²C, SPI Output")
      (fields
        (field (name "MANUFACTURER") "STMicroelectronics")
        (field (name "VENDOR PART NUMBER") "497-19784-1-ND")
        (field (name "CREATEDBY") "Judd Foster")
      )
      (libsource (lib "symbols") (part "ISM330DHCXTR"))
    )
    (comp (ref "U10")
      (value "PCF85063ATL/1,118")
      (footprint "IC,DFN-10_3x3,P0.5mm")
      (description "Real Time Clock (RTC) IC Clock/Calendar - I²C, 2-Wire Serial 10-XFDFN Exposed Pad")
      (fields
        (field (name "MANUFACTURER") "NXP USA Inc.")
        (field (name "VENDOR PART NUMBER") "568-10235-1-ND")
        (field (name "CREATEDBY") "Judd Foster")
      )
      (libsource (lib "symbols") (part "PCF85063ATL/1,118"))
    )
    (comp (ref "Y2")
      (value "32.768kHz")
      (footprint "XTAL,SMD,2PIN,2.0x1.2MM")
      (description "32.768 kHz ±20ppm Crystal 9pF 70 kOhms 2-SMD, No Lead")
      (fields
        (field (name "MANUFACTURER") "Micro Crystal AG")
        (field (name "MANUFACTURER PART NUMBER") "CM8V-T1A-32.768KHZ-9PF-20PPM-TA-QC")
        (field (name "CREATEDBY") "Judd Foster")
      )
      (libsource (lib "symbols") (part "XTAL,32.768kHz,9pF,SMD"))
    )
  )
  (nets
    (net (code "1") (name "/BIAS_OPAMP") (class "Default")
      (node (ref "R29") (pin "2") (pinfunction "2_2") (pintype "passive"))
      (node (ref "TP19") (pin "1") (pinfunction "TP_1") (pintype "passive"))
      (node (ref "U6") (pin "14") (pinfunction "VOUTR_14") (pintype "output"))
    )
    (net (code "2") (name "/ESP32_USB_N") (class "Default")
      (node (ref "U1") (pin "18") (pinfunction "GPIO13_18") (pintype "passive"))
    )
    (net (code "3") (name "/ESP32_USB_P") (class "Default")
      (node (ref "U1") (pin "19") (pinfunction "GPIO14_19") (pintype "passive"))
    )
    (net (code "4") (name "/I2C_SCL") (class "Default")
      (node (ref "R50") (pin "1") (pinfunction "1_1") (pintype "passive"))
      (node (ref "TP38") (pin "1") (pinfunction "TP_1") (pintype "passive"))
      (node (ref "U1") (pin "38") (pinfunction "GPIO33_38") (pintype "passive"))
      (node (ref "U10") (pin "7") (pinfunction "SCL_7") (pintype "passive"))
      (node (ref "U8") (pin "A2") (pinfunction "SCL_A2") (pintype "passive"))
      (node (ref "U9") (pin "13") (pinfunction "SCL_13") (pintype "passive"))
    )
    (net (code "5") (name "/I2C_SDA") (class "Default")
      (node (ref "R51") (pin "1") (pinfunction "1_1") (pintype "passive"))
      (node (ref "TP37") (pin "1") (pinfunction "TP_1") (pintype "passive"))
      (node (ref "U1") (pin "27") (pinfunction "GPIO21_27") (pintype "passive"))
      (node (ref "U10") (pin "6") (pinfunction "SDA_6") (pintype "passive"))
      (node (ref "U8") (pin "B2") (pinfunction "SDA_B2") (pintype "passive"))
      (node (ref "U9") (pin "14") (pinfunction "SDA_14") (pintype "passive"))
    )
    (net (code "6") (name "/ISM330_INT1") (class "Default")
      (node (ref "TP35") (pin "1") (pinfunction "TP_1") (pintype "passive"))
      (node (ref "U1") (pin "25") (pinfunction "GPIO19_25") (pintype "passive"))
      (node (ref "U9") (pin "4") (pinfunction "INT1_4") (pintype "passive"))
    )
    (net (code "7") (name "/ISM330_INT2") (class "Default")
      (node (ref "TP36") (pin "1") (pinfunction "TP_1") (pintype "passive"))
      (node (ref "U1") (pin "26") (pinfunction "GPIO20_26") (pintype "passive"))
      (node (ref "U9") (pin "9") (pinfunction "INT2_9") (pintype "passive"))
    )
    (net (code "8") (name "/LOAD_CELL_IN") (class "Default")
      (node (ref "J3") (pin "2") (pinfunction "2_2") (pintype "passive"))
      (node (ref "R28") (pin "1") (pinfunction "1_1") (pintype "passive"))
      (node (ref "R31") (pin "1") (pinfunction "1_1") (pintype "passive"))
    )
    (net (code "9") (name "/MCP3561_CS") (class "Default")
      (node (ref "R44") (pin "1") (pinfunction "1_1") (pintype "passive"))
      (node (ref "TP22") (pin "1") (pinfunction "TP_1") (pintype "passive"))
      (node (ref "U1") (pin "12") (pinfunction "GPIO7_12") (pintype "passive"))
    )
    (net (code "10") (name "/MCP3561_IRQ") (class "Default")
      (node (ref "R43") (pin "1") (pinfunction "1_1") (pintype "passive"))
      (node (ref "R48") (pin "1") (pinfunction "1_1") (pintype "passive"))
      (node (ref "TP24") (pin "1") (pinfunction "TP_1") (pintype "passive"))
      (node (ref "U1") (pin "13") (pinfunction "GPIO8_13") (pintype "passive"))
    )
    (net (code "11") (name "/MCP3561_MCLK") (class "Default")
      (node (ref "R49") (pin "1") (pinfunction "1_1") (pintype "passive"))
      (node (ref "TP25") (pin "1") (pinfunction "TP_1") (pintype "passive"))
      (node (ref "U1") (pin "14") (pinfunction "GPIO9_14") (pintype "passive"))
    )
    (net (code "12") (name "/PCM1780_BCK") (class "Default")
      (node (ref "R78") (pin "1") (pinfunction "1_1") (pintype "passive"))
      (node (ref "TP20") (pin "1") (pinfunction "TP_1") (pintype "passive"))
      (node (ref "U1") (pin "10") (pinfunction "GPIO5_10") (pintype "passive"))
    )
    (net (code "13") (name "/PCM1780_DATA") (class "Default")
      (node (ref "R77") (pin "1") (pinfunction "1_1") (pintype "passive"))
      (node (ref "TP31") (pin "1") (pinfunction "TP_1") (pintype "passive"))
      (node (ref "U1") (pin "9") (pinfunction "GPIO4_9") (pintype "passive"))
    )
    (net (code "14") (name "/PCM1780_LRCK") (class "Default")
      (node (ref "R79") (pin "1") (pinfunction "1_1") (pintype "passive"))
      (node (ref "TP30") (pin "1") (pinfunction "TP_1") (pintype "passive"))
      (node (ref "U1") (pin "11") (pinfunction "GPIO6_11") (pintype "passive"))
    )
    (net (code "15") (name "/PCM1780_MC") (class "Default")
      (node (ref "R74") (pin "1") (pinfunction "1_1") (pintype "passive"))
      (node (ref "TP27") (pin "1") (pinfunction "TP_1") (pintype "passive"))
      (node (ref "U1") (pin "6") (pinfunction "GPIO1_6") (pintype "passive"))
    )
    (net (code "16") (name "/PCM1780_MD") (class "Default")
      (node (ref "R75") (pin "1") (pinfunction "1_1") (pintype "passive"))
      (node (ref "TP28") (pin "1") (pinfunction "TP_1") (pintype "passive"))
      (node (ref "U1") (pin "7") (pinfunction "GPIO2_7") (pintype "passive"))
    )
    (net (code "17") (name "/PCM1780_SCK") (class "Default")
      (node (ref "R76") (pin "1") (pinfunction "1_1") (pintype "passive"))
      (node (ref "TP29") (pin "1") (pinfunction "TP_1") (pintype "passive"))
      (node (ref "U1") (pin "8") (pinfunction "GPIO3_8") (pintype "passive"))
    )
    (net (code "18") (name "/PCM1780_~{MS}") (class "Default")
      (node (ref "R73") (pin "1") (pinfunction "1_1") (pintype "passive"))
      (node (ref "TP26") (pin "1") (pinfunction "TP_1") (pintype "passive"))
      (node (ref "U1") (pin "5") (pinfunction "GPIO0_5") (pintype "passive"))
    )
    (net (code "19") (name "/SD_CD") (class "Default")
      (node (ref "J4") (pin "9") (pinfunction "CD_9") (pintype "passive"))
      (node (ref "R57") (pin "1") (pinfunction "1_1") (pintype "passive"))
      (node (ref "TP39") (pin "1") (pinfunction "TP_1") (pintype "passive"))
      (node (ref "U1") (pin "39") (pinfunction "GPIO34_39") (pintype "passive"))
    )
    (net (code "20") (name "/SD_CLK") (class "Default")
      (node (ref "J4") (pin "5") (pinfunction "CLK_5") (pintype "passive"))
      (node (ref "TP41") (pin "1") (pinfunction "TP_1") (pintype "passive"))
      (node (ref "U1") (pin "41") (pinfunction "GPIO36_41") (pintype "passive"))
    )
    (net (code "21") (name "/SD_CS") (class "Default")
      (node (ref "J4") (pin "2") (pinfunction "CD/DATA3_2") (pintype "passive"))
      (node (ref "TP43") (pin "1") (pinfunction "TP_1") (pintype "passive"))
      (node (ref "U1") (pin "43") (pinfunction "GPIO38_43") (pintype "passive"))
    )
    (net (code "22") (name "/SD_MISO") (class "Default")
      (node (ref "J4") (pin "7") (pinfunction "DAT0_7") (pintype "passive"))
      (node (ref "TP40") (pin "1") (pinfunction "TP_1") (pintype "passive"))
      (node (ref "U1") (pin "40") (pinfunction "GPIO35_40") (pintype "passive"))
    )
    (net (code "23") (name "/SD_MOSI") (class "Default")
      (node (ref "J4") (pin "3") (pinfunction "CMD_3") (pintype "passive"))
      (node (ref "TP42") (pin "1") (pinfunction "TP_1") (pintype "passive"))
      (node (ref "U1") (pin "42") (pinfunction "GPIO37_42") (pintype "passive"))
    )
    (net (code "24") (name "/SPI_SCK") (class "Default")
      (node (ref "R45") (pin "1") (pinfunction "1_1") (pintype "passive"))
      (node (ref "TP21") (pin "1") (pinfunction "TP_1") (pintype "passive"))
      (node (ref "U1") (pin "17") (pinfunction "GPIO12_17") (pintype "passive"))
    )
    (net (code "25") (name "/SPI_SDI") (class "Default")
      (node (ref "R46") (pin "1") (pinfunction "1_1") (pintype "passive"))
      (node (ref "TP23") (pin "1") (pinfunction "TP_1") (pintype "passive"))
      (node (ref "U1") (pin "16") (pinfunction "GPIO11_16") (pintype "passive"))
    )
    (net (code "26") (name "/SPI_SDO") (class "Default")
      (node (ref "R47") (pin "1") (pinfunction "1_1") (pintype "passive"))
      (node (ref "TP32") (pin "1") (pinfunction "TP_1") (pintype "passive"))
      (node (ref "U1") (pin "15") (pinfunction "GPIO10_15") (pintype "passive"))
    )
    (net (code "27") (name "/UART_ESP32RX_AVRTX") (class "Default")
      (node (ref "R3") (pin "2") (pinfunction "2_2") (pintype "passive"))
      (node (ref "TP8") (pin "1") (pinfunction "TP_1") (pintype "passive"))
    )
    (net (code "28") (name "/UART_ESP32TX_AVRRX") (class "Default")
      (node (ref "TP7") (pin "1") (pinfunction "TP_1") (pintype "passive"))
      (node (ref "U1") (pin "23") (pinfunction "GPIO17_23") (pintype "passive"))
    )
    (net (code "29") (name "A_GND") (class "Default")
      (node (ref "C26") (pin "1") (pinfunction "1_1") (pintype "passive"))
      (node (ref "C27") (pin "1") (pinfunction "1_1") (pintype "passive"))
      (node (ref "C28") (pin "1") (pinfunction "1_1") (pintype "passive"))
      (node (ref "C29") (pin "2") (pinfunction "2_2") (pintype "passive"))
      (node (ref "C30") (pin "1") (pinfunction "1_1") (pintype "passive"))
      (node (ref "C31") (pin "1") (pinfunction "1_1") (pintype "passive"))
      (node (ref "C33") (pin "1") (pinfunction "1_1") (pintype "passive"))
      (node (ref "J3") (pin "3") (pinfunction "3_3") (pintype "passive"))
      (node (ref "NT1") (pin "2") (pinfunction "2_2") (pintype "passive"))
      (node (ref "R30") (pin "1") (pinfunction "1_1") (pintype "passive"))
      (node (ref "R38") (pin "1") (pinfunction "1_1") (pintype "passive"))
      (node (ref "R40") (pin "1") (pinfunction "1_1") (pintype "passive"))
      (node (ref "R52") (pin "1") (pinfunction "1_1") (pintype "passive"))
      (node (ref "U5") (pin "11") (pinfunction "V-_11") (pintype "power_in"))
      (node (ref "U5") (pin "17") (pinfunction "PAD_17") (pintype "power_in"))
      (node (ref "U6") (pin "12") (pinfunction "AGND_12") (pintype "power_in"))
      (node (ref "U7") (pin "10") (pinfunction "NC_10") (pintype "passive"))
      (node (ref "U7") (pin "11") (pinfunction "NC_11") (pintype "passive"))
      (node (ref "U7") (pin "12") (pinfunction "NC_12") (pintype "passive"))
      (node (ref "U7") (pin "2") (pinfunction "AGND_2") (pintype "passive"))
      (node (ref "U7") (pin "3") (pinfunction "REFIN-_3") (pintype "passive"))
      (node (ref "U7") (pin "7") (pinfunction "NC_7") (pintype "passive"))
      (node (ref "U7") (pin "8") (pinfunction "NC_8") (pintype "passive"))
      (node (ref "U7") (pin "9") (pinfunction "NC_9") (pintype "passive"))
    )
    (net (code "30") (name "GND") (class "Default")
      (node (ref "B1") (pin "2") (pinfunction "BATT_N_2") (pintype "passive"))
      (node (ref "C32") (pin "1") (pinfunction "1_1") (pintype "passive"))
      (node (ref "C34") (pin "2") (pinfunction "2_2") (pintype "passive"))
      (node (ref "C35") (pin "1") (pinfunction "1_1") (pintype "passive"))
      (node (ref "C36") (pin "1") (pinfunction "1_1") (pintype "passive"))
      (node (ref "C37") (pin "1") (pinfunction "1_1") (pintype "passive"))
      (node (ref "C38") (pin "1") (pinfunction "1_1") (pintype "passive"))
      (node (ref "D6") (pin "2") (pinfunction "K_2") (pintype "passive"))
      (node (ref "J4") (pin "6") (pinfunction "VSS_6") (pintype "passive"))
      (node (ref "NT1") (pin "1") (pinfunction "1_1") (pintype "passive"))
      (node (ref "R54") (pin "1") (pinfunction "1_1") (pintype "passive"))
      (node (ref "U10") (pin "11") (pinfunction "PAD_11") (pintype "passive"))
      (node (ref "U10") (pin "3") (pinfunction "CLKOE_3") (pintype "passive"))
      (node (ref "U10") (pin "5") (pinfunction "VSS_5") (pintype "passive"))
      (node (ref "U7") (pin "19") (pinfunction "DGND_19") (pintype "passive"))
      (node (ref "U8") (pin "A1") (pinfunction "VSA_A1") (pintype "passive"))
      (node (ref "U9") (pin "2") (pinfunction "SDx_2") (pintype "passive"))
      (node (ref "U9") (pin "3") (pinfunction "SCx_3") (pintype "passive"))
      (node (ref "U9") (pin "6") (pinfunction "GND_6") (pintype "passive"))
      (node (ref "U9") (pin "7") (pinfunction "GND_7") (pintype "passive"))
    )
    (net (code "31") (name "Net-(B1-BATT_P)") (class "Default")
      (node (ref "B1") (pin "1") (pinfunction "BATT_P_1") (pintype "passive"))
      (node (ref "TP45") (pin "1") (pinfunction "TP_1") (pintype "passive"))
      (node (ref "U10") (pin "10") (pinfunction "VDD_10") (pintype "passive"))
    )
    (net (code "32") (name "Net-(C31-Pad2)") (class "Default")
      (node (ref "C31") (pin "2") (pinfunction "2_2") (pintype "passive"))
      (node (ref "L5") (pin "1") (pinfunction "1_1") (pintype "passive"))
      (node (ref "R37") (pin "2") (pinfunction "2_2") (pintype "passive"))
    )
    (net (code "33") (name "Net-(D6-A)") (class "Default")
      (node (ref "D6") (pin "1") (pinfunction "A_1") (pintype "passive"))
      (node (ref "R55") (pin "1") (pinfunction "1_1") (pintype "passive"))
    )
    (net (code "34") (name "Net-(Q5A-B1)") (class "Default")
      (node (ref "Q5") (pin "2") (pinfunction "B1_2") (pintype "passive"))
      (node (ref "Q6") (pin "6") (pinfunction "C1_6") (pintype "passive"))
      (node (ref "R32") (pin "1") (pinfunction "1_1") (pintype "passive"))
      (node (ref "TP11") (pin "1") (pinfunction "TP_1") (pintype "passive"))
    )
    (net (code "35") (name "Net-(Q5A-E1)") (class "Default")
      (node (ref "Q5") (pin "1") (pinfunction "E1_1") (pintype "passive"))
      (node (ref "R39") (pin "1") (pinfunction "1_1") (pintype "passive"))
    )
    (net (code "36") (name "Net-(Q5B-B2)") (class "Default")
      (node (ref "Q5") (pin "5") (pinfunction "B2_5") (pintype "passive"))
      (node (ref "Q6") (pin "3") (pinfunction "C2_3") (pintype "passive"))
      (node (ref "R33") (pin "1") (pinfunction "1_1") (pintype "passive"))
      (node (ref "TP12") (pin "1") (pinfunction "TP_1") (pintype "passive"))
    )
    (net (code "37") (name "Net-(Q5B-E2)") (class "Default")
      (node (ref "Q5") (pin "4") (pinfunction "E2_4") (pintype "passive"))
      (node (ref "R36") (pin "1") (pinfunction "1_1") (pintype "passive"))
    )
    (net (code "38") (name "Net-(Q6A-B1)") (class "Default")
      (node (ref "Q6") (pin "2") (pinfunction "B1_2") (pintype "passive"))
      (node (ref "TP17") (pin "1") (pinfunction "TP_1") (pintype "passive"))
      (node (ref "U5") (pin "13") (pinfunction "IN4-_13") (pintype "input"))
      (node (ref "U5") (pin "14") (pinfunction "OUT4_14") (pintype "output"))
    )
    (net (code "39") (name "Net-(Q6A-E1)") (class "Default")
      (node (ref "Q6") (pin "1") (pinfunction "E1_1") (pintype "passive"))
      (node (ref "Q6") (pin "4") (pinfunction "E2_4") (pintype "passive"))
      (node (ref "R38") (pin "2") (pinfunction "2_2") (pintype "passive"))
    )
    (net (code "40") (name "Net-(Q6B-B2)") (class "Default")
      (node (ref "Q6") (pin "5") (pinfunction "B2_5") (pintype "passive"))
      (node (ref "R31") (pin "2") (pinfunction "2_2") (pintype "passive"))
    )
    (net (code "41") (name "Net-(TP10-TP)") (class "Default")
      (node (ref "R34") (pin "1") (pinfunction "1_1") (pintype "passive"))
      (node (ref "TP10") (pin "1") (pinfunction "TP_1") (pintype "passive"))
      (node (ref "U5") (pin "5") (pinfunction "OUT2_5") (pintype "output"))
      (node (ref "U7") (pin "5") (pinfunction "CH0_5") (pintype "passive"))
    )
    (net (code "42") (name "Net-(TP13-TP)") (class "Default")
      (node (ref "TP13") (pin "1") (pinfunction "TP_1") (pintype "passive"))
      (node (ref "U5") (pin "7") (pinfunction "~{SHDN}34_7") (pintype "power_in"))
    )
    (net (code "43") (name "Net-(TP14-TP)") (class "Default")
      (node (ref "TP14") (pin "1") (pinfunction "TP_1") (pintype "passive"))
      (node (ref "U5") (pin "12") (pinfunction "IN4+_12") (pintype "input"))
      (node (ref "U6") (pin "15") (pinfunction "VOUTL_15") (pintype "output"))
    )
    (net (code "44") (name "Net-(TP15-TP)") (class "Default")
      (node (ref "TP15") (pin "1") (pinfunction "TP_1") (pintype "passive"))
      (node (ref "U6") (pin "1") (pinfunction "ZEROL/NA_1") (pintype "output"))
    )
    (net (code "45") (name "Net-(TP16-TP)") (class "Default")
      (node (ref "TP16") (pin "1") (pinfunction "TP_1") (pintype "passive"))
      (node (ref "U6") (pin "16") (pinfunction "ZEROR/ZEROA_16") (pintype "output"))
    )
    (net (code "46") (name "Net-(TP18-TP)") (class "Default")
      (node (ref "R35") (pin "1") (pinfunction "1_1") (pintype "passive"))
      (node (ref "R41") (pin "2") (pinfunction "2_2") (pintype "passive"))
      (node (ref "TP18") (pin "1") (pinfunction "TP_1") (pintype "passive"))
      (node (ref "U5") (pin "15") (pinfunction "OUT1_15") (pintype "output"))
    )
    (net (code "47") (name "Net-(TP44-TP)") (class "Default")
      (node (ref "TP44") (pin "1") (pinfunction "TP_1") (pintype "passive"))
      (node (ref "U1") (pin "51") (pinfunction "GPIO45_51") (pintype "passive"))
    )
    (net (code "48") (name "Net-(U1C-GPIO18)") (class "Default")
      (node (ref "R3") (pin "1") (pinfunction "1_1") (pintype "passive"))
      (node (ref "U1") (pin "24") (pinfunction "GPIO18_24") (pintype "passive"))
    )
    (net (code "49") (name "Net-(U1C-GPIO46)") (class "Default")
      (node (ref "R55") (pin "2") (pinfunction "2_2") (pintype "passive"))
      (node (ref "U1") (pin "52") (pinfunction "GPIO46_52") (pintype "passive"))
    )
    (net (code "50") (name "Net-(U5A-IN1+)") (class "Default")
      (node (ref "R39") (pin "2") (pinfunction "2_2") (pintype "passive"))
      (node (ref "R40") (pin "2") (pinfunction "2_2") (pintype "passive"))
      (node (ref "U5") (pin "1") (pinfunction "IN1+_1") (pintype "input"))
    )
    (net (code "51") (name "Net-(U5A-IN1-)") (class "Default")
      (node (ref "R35") (pin "2") (pinfunction "2_2") (pintype "passive"))
      (node (ref "R36") (pin "2") (pinfunction "2_2") (pintype "passive"))
      (node (ref "U5") (pin "16") (pinfunction "IN1-_16") (pintype "input"))
    )
    (net (code "52") (name "Net-(U5B-IN2+)") (class "Default")
      (node (ref "R28") (pin "2") (pinfunction "2_2") (pintype "passive"))
      (node (ref "U5") (pin "3") (pinfunction "IN2+_3") (pintype "input"))
    )
    (net (code "53") (name "Net-(U5B-IN2-)") (class "Default")
      (node (ref "R27") (pin "2") (pinfunction "2_2") (pintype "passive"))
      (node (ref "R29") (pin "1") (pinfunction "1_1") (pintype "passive"))
      (node (ref "R30") (pin "2") (pinfunction "2_2") (pintype "passive"))
      (node (ref "R34") (pin "2") (pinfunction "2_2") (pintype "passive"))
      (node (ref "U5") (pin "10") (pinfunction "IN3+_10") (pintype "input"))
      (node (ref "U5") (pin "4") (pinfunction "IN2-_4") (pintype "input"))
    )
    (net (code "54") (name "Net-(U5C-IN3-)") (class "Default")
      (node (ref "U5") (pin "8") (pinfunction "OUT3_8") (pintype "output"))
      (node (ref "U5") (pin "9") (pinfunction "IN3-_9") (pintype "input"))
    )
    (net (code "55") (name "Net-(U6-BCK)") (class "Default")
      (node (ref "R78") (pin "2") (pinfunction "2_2") (pintype "passive"))
      (node (ref "U6") (pin "7") (pinfunction "BCK_7") (pintype "input"))
    )
    (net (code "56") (name "Net-(U6-DATA)") (class "Default")
      (node (ref "R77") (pin "2") (pinfunction "2_2") (pintype "passive"))
      (node (ref "U6") (pin "6") (pinfunction "DATA_6") (pintype "input"))
    )
    (net (code "57") (name "Net-(U6-LRCK)") (class "Default")
      (node (ref "R79") (pin "2") (pinfunction "2_2") (pintype "passive"))
      (node (ref "U6") (pin "8") (pinfunction "LRCK_8") (pintype "input"))
    )
    (net (code "58") (name "Net-(U6-MC)") (class "Default")
      (node (ref "R74") (pin "2") (pinfunction "2_2") (pintype "passive"))
      (node (ref "U6") (pin "3") (pinfunction "MC_3") (pintype "input"))
    )
    (net (code "59") (name "Net-(U6-MD)") (class "Default")
      (node (ref "R75") (pin "2") (pinfunction "2_2") (pintype "passive"))
      (node (ref "U6") (pin "4") (pinfunction "MD_4") (pintype "input"))
    )
    (net (code "60") (name "Net-(U6-SCK)") (class "Default")
      (node (ref "R76") (pin "2") (pinfunction "2_2") (pintype "passive"))
      (node (ref "U6") (pin "5") (pinfunction "SCK_5") (pintype "input"))
    )
    (net (code "61") (name "Net-(U6-VCOM)") (class "Default")
      (node (ref "C29") (pin "1") (pinfunction "1_1") (pintype "passive"))
      (node (ref "U6") (pin "13") (pinfunction "VCOM_13") (pintype "power_in"))
    )
    (net (code "62") (name "Net-(U6-~{MS})") (class "Default")
      (node (ref "R73") (pin "2") (pinfunction "2_2") (pintype "passive"))
      (node (ref "U6") (pin "2") (pinfunction "~{MS}_2") (pintype "input"))
    )
    (net (code "63") (name "Net-(U7-AVDD)") (class "Default")
      (node (ref "C30") (pin "2") (pinfunction "2_2") (pintype "passive"))
      (node (ref "R37") (pin "1") (pinfunction "1_1") (pintype "passive"))
      (node (ref "U7") (pin "1") (pinfunction "AVDD_1") (pintype "passive"))
    )
    (net (code "64") (name "Net-(U7-CH1)") (class "Default")
      (node (ref "R41") (pin "1") (pinfunction "1_1") (pintype "passive"))
      (node (ref "R52") (pin "2") (pinfunction "2_2") (pintype "passive"))
      (node (ref "U7") (pin "6") (pinfunction "CH1_6") (pintype "passive"))
    )
    (net (code "65") (name "Net-(U7-DVDD)") (class "Default")
      (node (ref "C32") (pin "2") (pinfunction "2_2") (pintype "passive"))
      (node (ref "R42") (pin "1") (pinfunction "1_1") (pintype "passive"))
      (node (ref "U7") (pin "20") (pinfunction "DVDD_20") (pintype "passive"))
    )
    (net (code "66") (name "Net-(U7-MCLK)") (class "Default")
      (node (ref "R49") (pin "2") (pinfunction "2_2") (pintype "passive"))
      (node (ref "U7") (pin "18") (pinfunction "MCLK_18") (pintype "passive"))
    )
    (net (code "67") (name "Net-(U7-REFIN+{slash}OUT)") (class "Default")
      (node (ref "C33") (pin "2") (pinfunction "2_2") (pintype "passive"))
      (node (ref "U7") (pin "4") (pinfunction "REFIN+/OUT_4") (pintype "passive"))
    )
    (net (code "68") (name "Net-(U7-SCK)") (class "Default")
      (node (ref "R45") (pin "2") (pinfunction "2_2") (pintype "passive"))
      (node (ref "U7") (pin "14") (pinfunction "SCK_14") (pintype "passive"))
    )
    (net (code "69") (name "Net-(U7-SDI)") (class "Default")
      (node (ref "R46") (pin "2") (pinfunction "2_2") (pintype "passive"))
      (node (ref "U7") (pin "15") (pinfunction "SDI_15") (pintype "passive"))
    )
    (net (code "70") (name "Net-(U7-SDO)") (class "Default")
      (node (ref "R47") (pin "2") (pinfunction "2_2") (pintype "passive"))
      (node (ref "U7") (pin "16") (pinfunction "SDO_16") (pintype "passive"))
    )
    (net (code "71") (name "Net-(U7-~{CS})") (class "Default")
      (node (ref "R44") (pin "2") (pinfunction "2_2") (pintype "passive"))
      (node (ref "U7") (pin "13") (pinfunction "~{CS}_13") (pintype "passive"))
    )
    (net (code "72") (name "Net-(U7-~{IRQ}{slash}MDAT)") (class "Default")
      (node (ref "R48") (pin "2") (pinfunction "2_2") (pintype "passive"))
      (node (ref "U7") (pin "17") (pinfunction "~{IRQ}/MDAT_17") (pintype "passive"))
    )
    (net (code "73") (name "Net-(U9-SDO{slash}SA0)") (class "Default")
      (node (ref "R53") (pin "2") (pinfunction "2_2") (pintype "passive"))
      (node (ref "R54") (pin "2") (pinfunction "2_2") (pintype "passive"))
      (node (ref "U9") (pin "1") (pinfunction "SDO/SA0_1") (pintype "passive"))
    )
    (net (code "74") (name "Net-(U10-OSCI)") (class "Default")
      (node (ref "U10") (pin "1") (pinfunction "OSCI_1") (pintype "passive"))
      (node (ref "Y2") (pin "2") (pinfunction "GND_2") (pintype "passive"))
    )
    (net (code "75") (name "Net-(U10-OSCO)") (class "Default")
      (node (ref "U10") (pin "2") (pinfunction "OSCO_2") (pintype "passive"))
      (node (ref "Y2") (pin "1") (pinfunction "OSC1_1") (pintype "passive"))
    )
    (net (code "76") (name "VDD_3V3") (class "Default")
      (node (ref "C34") (pin "1") (pinfunction "1_1") (pintype "passive"))
      (node (ref "C35") (pin "2") (pinfunction "2_2") (pintype "passive"))
      (node (ref "C36") (pin "2") (pinfunction "2_2") (pintype "passive"))
      (node (ref "C37") (pin "2") (pinfunction "2_2") (pintype "passive"))
      (node (ref "C38") (pin "2") (pinfunction "2_2") (pintype "passive"))
      (node (ref "J4") (pin "4") (pinfunction "VDD_4") (pintype "passive"))
      (node (ref "L5") (pin "2") (pinfunction "2_2") (pintype "passive"))
      (node (ref "R42") (pin "2") (pinfunction "2_2") (pintype "passive"))
      (node (ref "R43") (pin "2") (pinfunction "2_2") (pintype "passive"))
      (node (ref "R50") (pin "2") (pinfunction "2_2") (pintype "passive"))
      (node (ref "R51") (pin "2") (pinfunction "2_2") (pintype "passive"))
      (node (ref "R53") (pin "1") (pinfunction "1_1") (pintype "passive"))
      (node (ref "R57") (pin "2") (pinfunction "2_2") (pintype "passive"))
      (node (ref "U8") (pin "B1") (pinfunction "VDD_B1") (pintype "passive"))
      (node (ref "U9") (pin "12") (pinfunction "CS_12") (pintype "passive"))
      (node (ref "U9") (pin "5") (pinfunction "VDDIO_5") (pintype "passive"))
      (node (ref "U9") (pin "8") (pinfunction "VDD_8") (pintype "passive"))
    )
    (net (code "77") (name "VDD_5VA") (class "Default")
      (node (ref "C26") (pin "2") (pinfunction "2_2") (pintype "passive"))
      (node (ref "C27") (pin "2") (pinfunction "2_2") (pintype "passive"))
      (node (ref "C28") (pin "2") (pinfunction "2_2") (pintype "passive"))
      (node (ref "J3") (pin "1") (pinfunction "1_1") (pintype "passive"))
      (node (ref "Q5") (pin "3") (pinfunction "C2_3") (pintype "passive"))
      (node (ref "Q5") (pin "6") (pinfunction "C1_6") (pintype "passive"))
      (node (ref "R27") (pin "1") (pinfunction "1_1") (pintype "passive"))
      (node (ref "R32") (pin "2") (pinfunction "2_2") (pintype "passive"))
      (node (ref "R33") (pin "2") (pinfunction "2_2") (pintype "passive"))
      (node (ref "U5") (pin "2") (pinfunction "V+_2") (pintype "power_in"))
      (node (ref "U5") (pin "6") (pinfunction "~{SHDN}12_6") (pintype "power_in"))
      (node (ref "U6") (pin "11") (pinfunction "VCC_11") (pintype "power_in"))
    )
    (net (code "78") (name "unconnected-(J4-DAT1-Pad8)") (class "Default")
      (node (ref "J4") (pin "8") (pinfunction "DAT1_8") (pintype "passive+no_connect"))
    )
    (net (code "79") (name "unconnected-(J4-DAT2-Pad1)") (class "Default")
      (node (ref "J4") (pin "1") (pinfunction "DAT2_1") (pintype "passive+no_connect"))
    )
    (net (code "80") (name "unconnected-(U6-NC-Pad9)") (class "Default")
      (node (ref "U6") (pin "9") (pinfunction "NC_9") (pintype "passive+no_connect"))
    )
    (net (code "81") (name "unconnected-(U6-NC-Pad10)") (class "Default")
      (node (ref "U6") (pin "10") (pinfunction "NC_10") (pintype "passive+no_connect"))
    )
    (net (code "82") (name "unconnected-(U9-OCS_AUX-Pad10)") (class "Default")
      (node (ref "U9") (pin "10") (pinfunction "OCS_AUX_10") (pintype "passive+no_connect"))
    )
    (net (code "83") (name "unconnected-(U9-SDO_AUX-Pad11)") (class "Default")
      (node (ref "U9") (pin "11") (pinfunction "SDO_AUX_11") (pintype "passive+no_connect"))
    )
    (net (code "84") (name "unconnected-(U10-CLKOUT-Pad9)") (class "Default")
      (node (ref "U10") (pin "9") (pinfunction "CLKOUT_9") (pintype "passive+no_connect"))
    )
    (net (code "85") (name "unconnected-(U10-NC-Pad8)") (class "Default")
      (node (ref "U10") (pin "8") (pinfunction "NC_8") (pintype "passive+no_connect"))
    )
    (net (code "86") (name "unconnected-(U10-~{INT}-Pad4)") (class "Default")
      (node (ref "U10") (pin "4") (pinfunction "~{INT}_4") (pintype "passive+no_connect"))
    )
  )
)
